# uP.net
KiCad netlist of a schematic drawn in Altium Designer
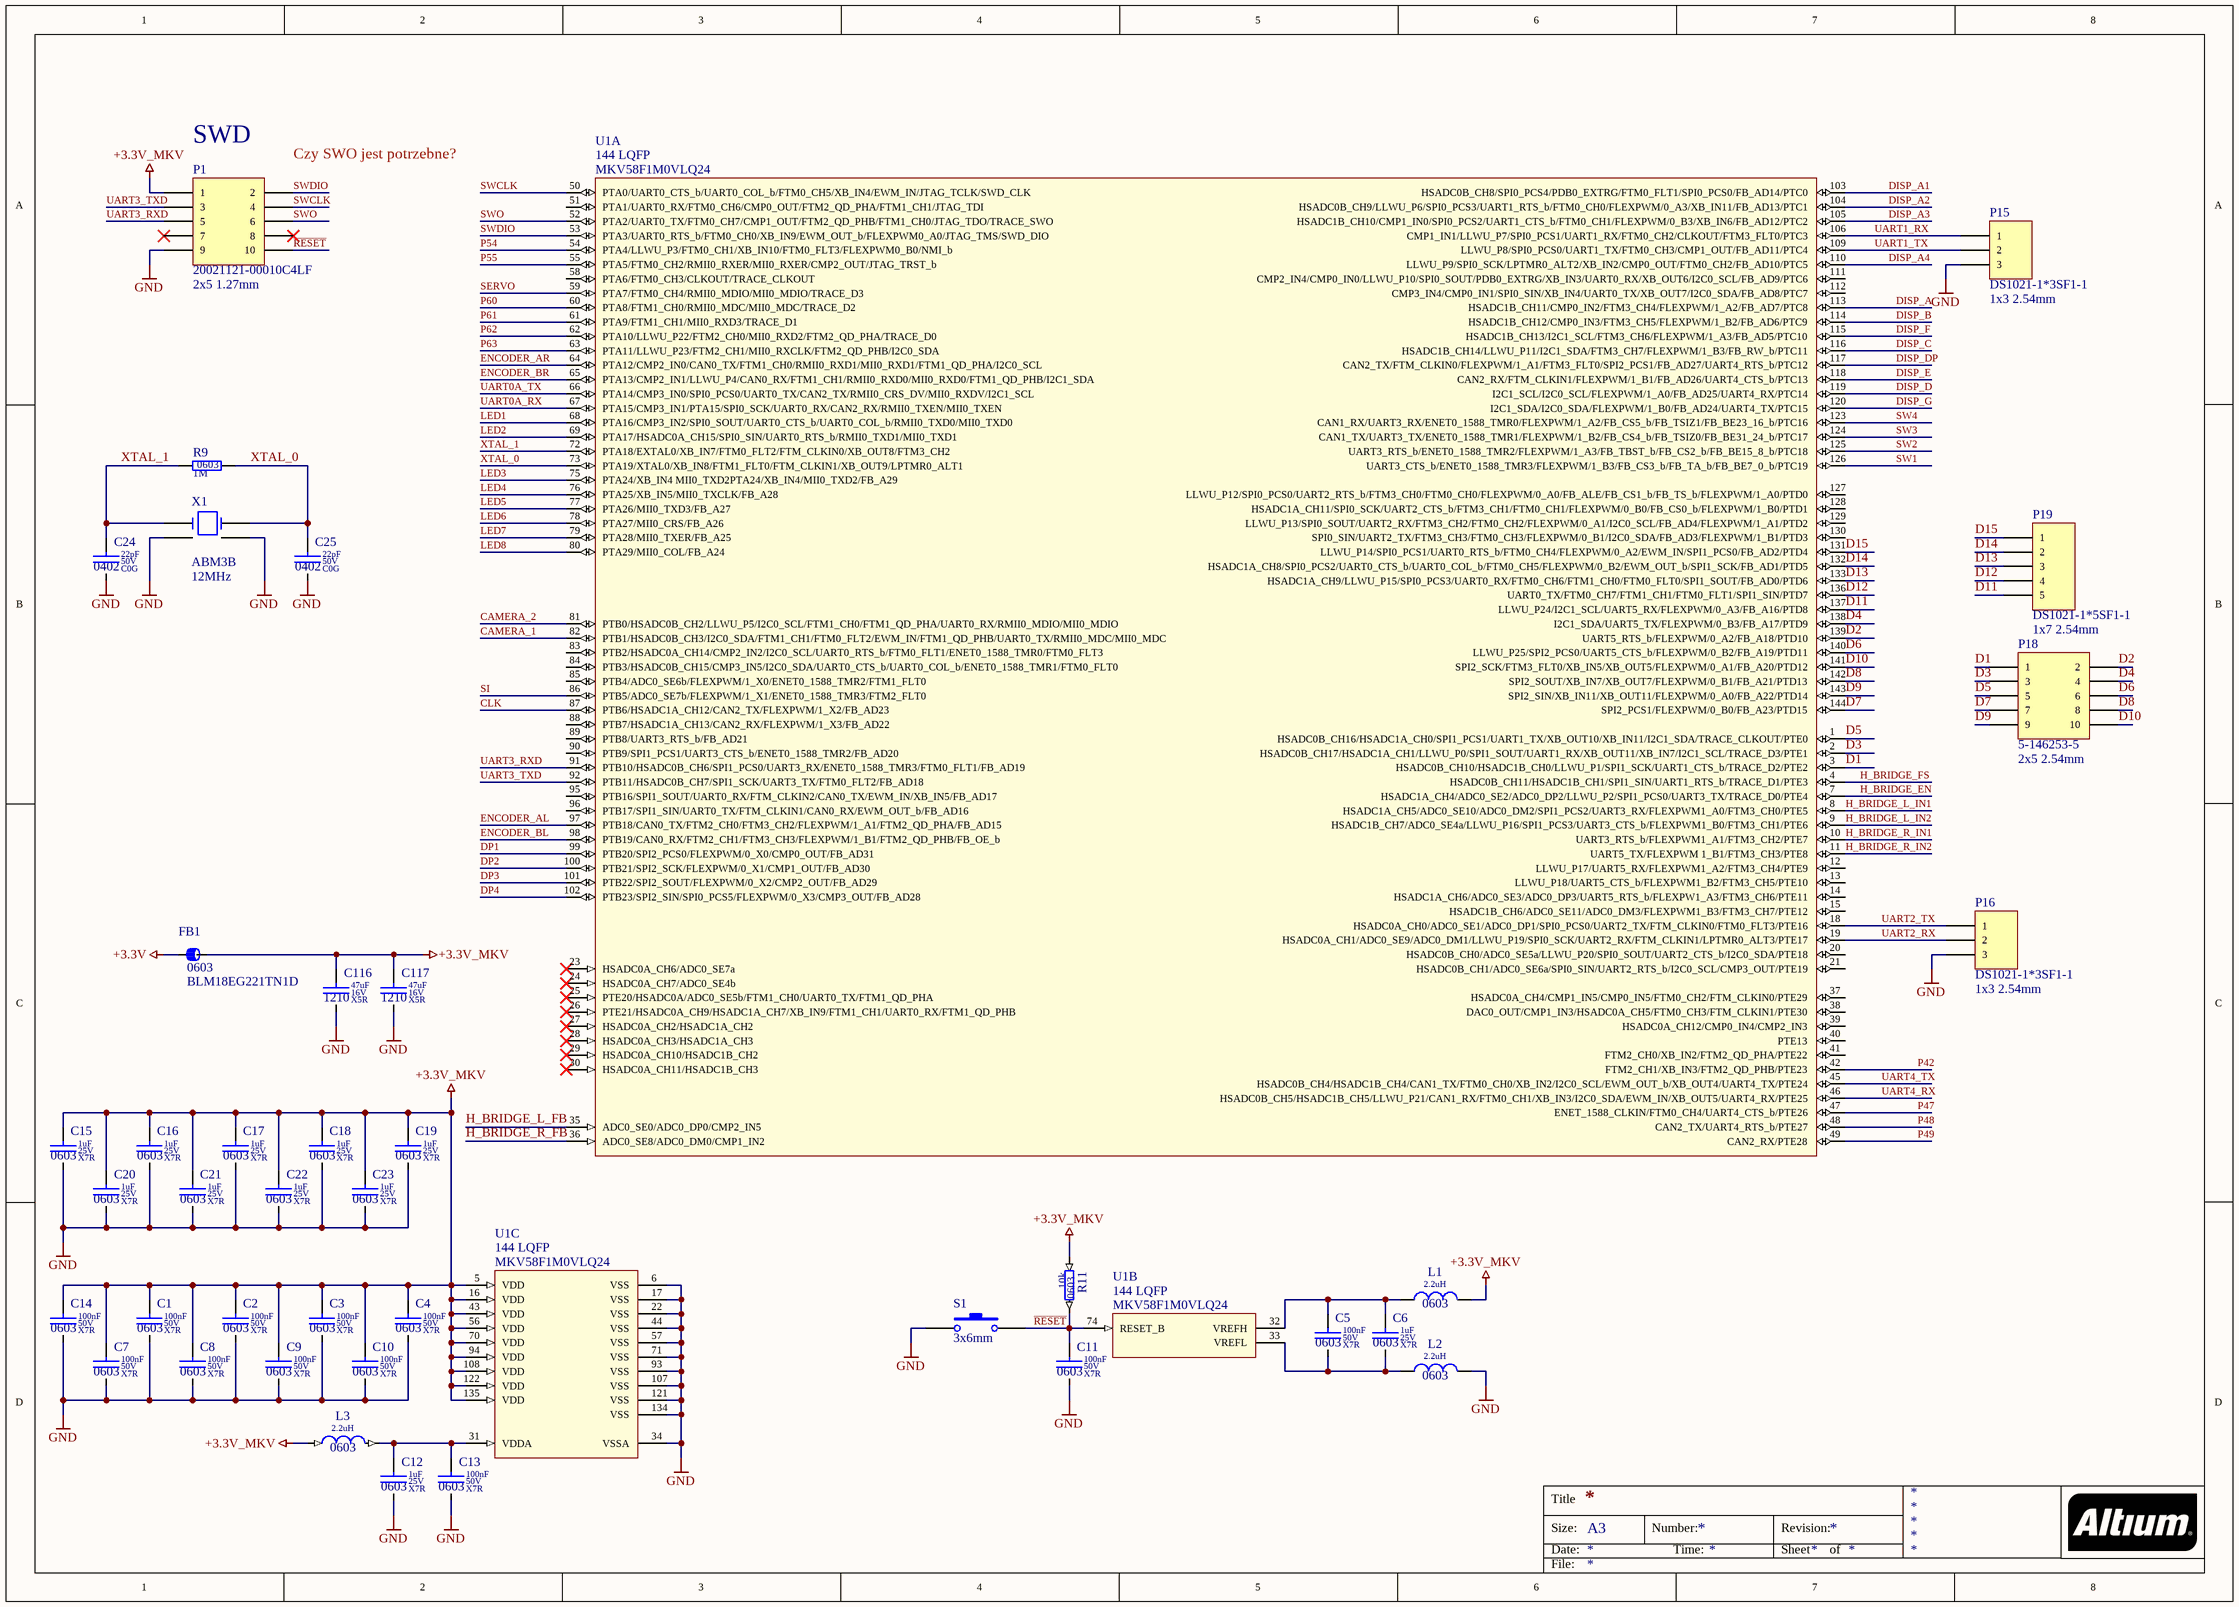
[diagram p0: uP.SchDoc]

(export (version "E")
  (design (tool "Eeschema 10.0.6"))
  (components
    (comp (ref "C1")
      (value "100nF")
      (footprint "C_0603_1608")
      (description "Capacitor")
      (fields
        (field (name "DIELECTRIC") "X7R")
        (field (name "VOLTAGE") "50V")
        (field (name "SCH_FOOTPRINT") "0603")
        (field (name "PART NUMBER") "C_100nF_50V_X7R_0603_5")
        (field (name "MANUFACTURER") "Samsung")
      )
      (libsource (lib "Library") (part "C"))
    )
    (comp (ref "C2")
      (value "100nF")
      (footprint "C_0603_1608")
      (description "Capacitor")
      (fields
        (field (name "DIELECTRIC") "X7R")
        (field (name "VOLTAGE") "50V")
        (field (name "SCH_FOOTPRINT") "0603")
        (field (name "PART NUMBER") "C_100nF_50V_X7R_0603_5")
        (field (name "MANUFACTURER") "Samsung")
      )
      (libsource (lib "Library") (part "C"))
    )
    (comp (ref "C3")
      (value "100nF")
      (footprint "C_0603_1608")
      (description "Capacitor")
      (fields
        (field (name "DIELECTRIC") "X7R")
        (field (name "VOLTAGE") "50V")
        (field (name "SCH_FOOTPRINT") "0603")
        (field (name "PART NUMBER") "C_100nF_50V_X7R_0603_5")
        (field (name "MANUFACTURER") "Samsung")
      )
      (libsource (lib "Library") (part "C"))
    )
    (comp (ref "C4")
      (value "100nF")
      (footprint "C_0603_1608")
      (description "Capacitor")
      (fields
        (field (name "DIELECTRIC") "X7R")
        (field (name "VOLTAGE") "50V")
        (field (name "SCH_FOOTPRINT") "0603")
        (field (name "PART NUMBER") "C_100nF_50V_X7R_0603_5")
        (field (name "MANUFACTURER") "Samsung")
      )
      (libsource (lib "Library") (part "C"))
    )
    (comp (ref "C5")
      (value "100nF")
      (footprint "C_0603_1608")
      (description "Capacitor")
      (fields
        (field (name "DIELECTRIC") "X7R")
        (field (name "VOLTAGE") "50V")
        (field (name "SCH_FOOTPRINT") "0603")
        (field (name "PART NUMBER") "C_100nF_50V_X7R_0603_5")
        (field (name "MANUFACTURER") "Samsung")
      )
      (libsource (lib "Library") (part "C"))
    )
    (comp (ref "C6")
      (value "1uF")
      (footprint "C_0603_1608")
      (description "Capacitor")
      (fields
        (field (name "DIELECTRIC") "X7R")
        (field (name "VOLTAGE") "25V")
        (field (name "SCH_FOOTPRINT") "0603")
        (field (name "PART NUMBER") "C_1uF_25V_X7R_0603_10")
        (field (name "MANUFACTURER") "Samsung")
      )
      (libsource (lib "Library") (part "C"))
    )
    (comp (ref "C7")
      (value "100nF")
      (footprint "C_0603_1608")
      (description "Capacitor")
      (fields
        (field (name "DIELECTRIC") "X7R")
        (field (name "VOLTAGE") "50V")
        (field (name "SCH_FOOTPRINT") "0603")
        (field (name "PART NUMBER") "C_100nF_50V_X7R_0603_5")
        (field (name "MANUFACTURER") "Samsung")
      )
      (libsource (lib "Library") (part "C"))
    )
    (comp (ref "C8")
      (value "100nF")
      (footprint "C_0603_1608")
      (description "Capacitor")
      (fields
        (field (name "DIELECTRIC") "X7R")
        (field (name "VOLTAGE") "50V")
        (field (name "SCH_FOOTPRINT") "0603")
        (field (name "PART NUMBER") "C_100nF_50V_X7R_0603_5")
        (field (name "MANUFACTURER") "Samsung")
      )
      (libsource (lib "Library") (part "C"))
    )
    (comp (ref "C9")
      (value "100nF")
      (footprint "C_0603_1608")
      (description "Capacitor")
      (fields
        (field (name "DIELECTRIC") "X7R")
        (field (name "VOLTAGE") "50V")
        (field (name "SCH_FOOTPRINT") "0603")
        (field (name "PART NUMBER") "C_100nF_50V_X7R_0603_5")
        (field (name "MANUFACTURER") "Samsung")
      )
      (libsource (lib "Library") (part "C"))
    )
    (comp (ref "C10")
      (value "100nF")
      (footprint "C_0603_1608")
      (description "Capacitor")
      (fields
        (field (name "DIELECTRIC") "X7R")
        (field (name "VOLTAGE") "50V")
        (field (name "SCH_FOOTPRINT") "0603")
        (field (name "PART NUMBER") "C_100nF_50V_X7R_0603_5")
        (field (name "MANUFACTURER") "Samsung")
      )
      (libsource (lib "Library") (part "C"))
    )
    (comp (ref "C11")
      (value "100nF")
      (footprint "C_0603_1608")
      (description "Capacitor")
      (fields
        (field (name "DIELECTRIC") "X7R")
        (field (name "VOLTAGE") "50V")
        (field (name "SCH_FOOTPRINT") "0603")
        (field (name "PART NUMBER") "C_100nF_50V_X7R_0603_5")
        (field (name "MANUFACTURER") "Samsung")
      )
      (libsource (lib "Library") (part "C"))
    )
    (comp (ref "C12")
      (value "1uF")
      (footprint "C_0603_1608")
      (description "Capacitor")
      (fields
        (field (name "DIELECTRIC") "X7R")
        (field (name "VOLTAGE") "25V")
        (field (name "SCH_FOOTPRINT") "0603")
        (field (name "PART NUMBER") "C_1uF_25V_X7R_0603_10")
        (field (name "MANUFACTURER") "Samsung")
      )
      (libsource (lib "Library") (part "C"))
    )
    (comp (ref "C13")
      (value "100nF")
      (footprint "C_0603_1608")
      (description "Capacitor")
      (fields
        (field (name "DIELECTRIC") "X7R")
        (field (name "VOLTAGE") "50V")
        (field (name "SCH_FOOTPRINT") "0603")
        (field (name "PART NUMBER") "C_100nF_50V_X7R_0603_5")
        (field (name "MANUFACTURER") "Samsung")
      )
      (libsource (lib "Library") (part "C"))
    )
    (comp (ref "C14")
      (value "100nF")
      (footprint "C_0603_1608")
      (description "Capacitor")
      (fields
        (field (name "DIELECTRIC") "X7R")
        (field (name "VOLTAGE") "50V")
        (field (name "SCH_FOOTPRINT") "0603")
        (field (name "PART NUMBER") "C_100nF_50V_X7R_0603_5")
        (field (name "MANUFACTURER") "Samsung")
      )
      (libsource (lib "Library") (part "C"))
    )
    (comp (ref "C15")
      (value "1uF")
      (footprint "C_0603_1608")
      (description "Capacitor")
      (fields
        (field (name "DIELECTRIC") "X7R")
        (field (name "VOLTAGE") "25V")
        (field (name "SCH_FOOTPRINT") "0603")
        (field (name "PART NUMBER") "C_1uF_25V_X7R_0603_10")
        (field (name "MANUFACTURER") "Samsung")
      )
      (libsource (lib "Library") (part "C"))
    )
    (comp (ref "C16")
      (value "1uF")
      (footprint "C_0603_1608")
      (description "Capacitor")
      (fields
        (field (name "DIELECTRIC") "X7R")
        (field (name "VOLTAGE") "25V")
        (field (name "SCH_FOOTPRINT") "0603")
        (field (name "PART NUMBER") "C_1uF_25V_X7R_0603_10")
        (field (name "MANUFACTURER") "Samsung")
      )
      (libsource (lib "Library") (part "C"))
    )
    (comp (ref "C17")
      (value "1uF")
      (footprint "C_0603_1608")
      (description "Capacitor")
      (fields
        (field (name "DIELECTRIC") "X7R")
        (field (name "VOLTAGE") "25V")
        (field (name "SCH_FOOTPRINT") "0603")
        (field (name "PART NUMBER") "C_1uF_25V_X7R_0603_10")
        (field (name "MANUFACTURER") "Samsung")
      )
      (libsource (lib "Library") (part "C"))
    )
    (comp (ref "C18")
      (value "1uF")
      (footprint "C_0603_1608")
      (description "Capacitor")
      (fields
        (field (name "DIELECTRIC") "X7R")
        (field (name "VOLTAGE") "25V")
        (field (name "SCH_FOOTPRINT") "0603")
        (field (name "PART NUMBER") "C_1uF_25V_X7R_0603_10")
        (field (name "MANUFACTURER") "Samsung")
      )
      (libsource (lib "Library") (part "C"))
    )
    (comp (ref "C19")
      (value "1uF")
      (footprint "C_0603_1608")
      (description "Capacitor")
      (fields
        (field (name "DIELECTRIC") "X7R")
        (field (name "VOLTAGE") "25V")
        (field (name "SCH_FOOTPRINT") "0603")
        (field (name "PART NUMBER") "C_1uF_25V_X7R_0603_10")
        (field (name "MANUFACTURER") "Samsung")
      )
      (libsource (lib "Library") (part "C"))
    )
    (comp (ref "C20")
      (value "1uF")
      (footprint "C_0603_1608")
      (description "Capacitor")
      (fields
        (field (name "DIELECTRIC") "X7R")
        (field (name "VOLTAGE") "25V")
        (field (name "SCH_FOOTPRINT") "0603")
        (field (name "PART NUMBER") "C_1uF_25V_X7R_0603_10")
        (field (name "MANUFACTURER") "Samsung")
      )
      (libsource (lib "Library") (part "C"))
    )
    (comp (ref "C21")
      (value "1uF")
      (footprint "C_0603_1608")
      (description "Capacitor")
      (fields
        (field (name "DIELECTRIC") "X7R")
        (field (name "VOLTAGE") "25V")
        (field (name "SCH_FOOTPRINT") "0603")
        (field (name "PART NUMBER") "C_1uF_25V_X7R_0603_10")
        (field (name "MANUFACTURER") "Samsung")
      )
      (libsource (lib "Library") (part "C"))
    )
    (comp (ref "C22")
      (value "1uF")
      (footprint "C_0603_1608")
      (description "Capacitor")
      (fields
        (field (name "DIELECTRIC") "X7R")
        (field (name "VOLTAGE") "25V")
        (field (name "SCH_FOOTPRINT") "0603")
        (field (name "PART NUMBER") "C_1uF_25V_X7R_0603_10")
        (field (name "MANUFACTURER") "Samsung")
      )
      (libsource (lib "Library") (part "C"))
    )
    (comp (ref "C23")
      (value "1uF")
      (footprint "C_0603_1608")
      (description "Capacitor")
      (fields
        (field (name "DIELECTRIC") "X7R")
        (field (name "VOLTAGE") "25V")
        (field (name "SCH_FOOTPRINT") "0603")
        (field (name "PART NUMBER") "C_1uF_25V_X7R_0603_10")
        (field (name "MANUFACTURER") "Samsung")
      )
      (libsource (lib "Library") (part "C"))
    )
    (comp (ref "C24")
      (value "22pF")
      (footprint "C_0402_1005")
      (description "Capacitor")
      (fields
        (field (name "DIELECTRIC") "C0G")
        (field (name "VOLTAGE") "50V")
        (field (name "SCH_FOOTPRINT") "0402")
        (field (name "PART NUMBER") "C_22pF_50V_C0G_0402_5")
        (field (name "MANUFACTURER") "AVX")
      )
      (libsource (lib "Library") (part "C"))
    )
    (comp (ref "C25")
      (value "22pF")
      (footprint "C_0402_1005")
      (description "Capacitor")
      (fields
        (field (name "DIELECTRIC") "C0G")
        (field (name "VOLTAGE") "50V")
        (field (name "SCH_FOOTPRINT") "0402")
        (field (name "PART NUMBER") "C_22pF_50V_C0G_0402_5")
        (field (name "MANUFACTURER") "AVX")
      )
      (libsource (lib "Library") (part "C"))
    )
    (comp (ref "C116")
      (value "47uF")
      (footprint "C_1210_3225")
      (description "Capacitor")
      (fields
        (field (name "DIELECTRIC") "X5R")
        (field (name "VOLTAGE") "16V")
        (field (name "SCH_FOOTPRINT") "1210")
        (field (name "PART NUMBER") "C_47uF_16V_X5R_1210_10")
        (field (name "MANUFACTURER") "Samsung")
      )
      (libsource (lib "Library") (part "C"))
    )
    (comp (ref "C117")
      (value "47uF")
      (footprint "C_1210_3225")
      (description "Capacitor")
      (fields
        (field (name "DIELECTRIC") "X5R")
        (field (name "VOLTAGE") "16V")
        (field (name "SCH_FOOTPRINT") "1210")
        (field (name "PART NUMBER") "C_47uF_16V_X5R_1210_10")
        (field (name "MANUFACTURER") "Samsung")
      )
      (libsource (lib "Library") (part "C"))
    )
    (comp (ref "FB1")
      (value "BLM18EG221TN1D")
      (footprint "FB_0603_1608")
      (description "Ferrite Bead")
      (fields
        (field (name "PART NUMBER") "FB_BLM18EG221TN1D")
        (field (name "SCH_FOOTPRINT") "0603")
        (field (name "MANUFACTURER") "Murata")
      )
      (libsource (lib "Library") (part "FB"))
    )
    (comp (ref "L1")
      (value "2.2uH")
      (footprint "L_0603_1608")
      (description "Induction")
      (fields
        (field (name "SCH_FOOTPRINT") "0603")
        (field (name "PART NUMBER") "L_2.2uH_130mA_0603")
        (field (name "MANUFACTURER") "TDK")
      )
      (libsource (lib "") (part "L_1"))
    )
    (comp (ref "L2")
      (value "2.2uH")
      (footprint "L_0603_1608")
      (description "Induction")
      (fields
        (field (name "SCH_FOOTPRINT") "0603")
        (field (name "PART NUMBER") "L_2.2uH_130mA_0603")
        (field (name "MANUFACTURER") "TDK")
      )
      (libsource (lib "") (part "L_1"))
    )
    (comp (ref "L3")
      (value "2.2uH")
      (footprint "L_0603_1608")
      (description "Induction")
      (fields
        (field (name "SCH_FOOTPRINT") "0603")
        (field (name "PART NUMBER") "L_2.2uH_130mA_0603")
        (field (name "MANUFACTURER") "TDK")
      )
      (libsource (lib "Library") (part "L"))
    )
    (comp (ref "P1")
      (value "20021121-00010C4LF")
      (footprint "P_HEADER_2x5_1.27")
      (description "Header, 10-Pin, Dual row")
      (fields
        (field (name "PART NUMBER") "P_HEADER_2x5_1.27")
        (field (name "SCH_FOOTPRINT") "2x5 1.27mm")
        (field (name "MANUFACTURER") "FCI")
      )
      (libsource (lib "Library") (part "P_HEADER_2x5"))
    )
    (comp (ref "P15")
      (value "DS1021-1*3SF1-1")
      (footprint "P_HEADER_1x3_2.54")
      (description "Header, 3-Pin")
      (fields
        (field (name "PART NUMBER") "P_HEADER_1x3_2.54")
        (field (name "SCH_FOOTPRINT") "1x3 2.54mm")
        (field (name "MANUFACTURER") "Connfly")
      )
      (libsource (lib "Library") (part "P_HEADER_1x3"))
    )
    (comp (ref "P16")
      (value "DS1021-1*3SF1-1")
      (footprint "P_HEADER_1x3_2.54")
      (description "Header, 3-Pin")
      (fields
        (field (name "PART NUMBER") "P_HEADER_1x3_2.54")
        (field (name "SCH_FOOTPRINT") "1x3 2.54mm")
        (field (name "MANUFACTURER") "Connfly")
      )
      (libsource (lib "Library") (part "P_HEADER_1x3"))
    )
    (comp (ref "P18")
      (value "5-146253-5")
      (footprint "P_HEADER_2x5_2.54")
      (description "Header, 10-Pin, Dual row")
      (fields
        (field (name "PART NUMBER") "P_HEADER_2x5_2.54")
        (field (name "SCH_FOOTPRINT") "2x5 2.54mm")
        (field (name "MANUFACTURER") "TE Connectivity")
      )
      (libsource (lib "Library") (part "P_HEADER_2x5"))
    )
    (comp (ref "P19")
      (value "DS1021-1*5SF1-1")
      (footprint "P_HEADER_1x5_2.54")
      (description "Header, 5-Pin")
      (fields
        (field (name "PART NUMBER") "P_HEADER_1x5_2.54")
        (field (name "SCH_FOOTPRINT") "1x7 2.54mm")
        (field (name "MANUFACTURER") "Connfly")
      )
      (libsource (lib "Library") (part "P_HEADER_1x5"))
    )
    (comp (ref "R9")
      (value "1M")
      (footprint "R_0603_1608")
      (fields
        (field (name "SCH_FOOTPRINT") "0603")
        (field (name "PART NUMBER") "R_1M_0603_1")
        (field (name "VOLTAGE") "50V")
        (field (name "POWER") "100mW")
      )
      (libsource (lib "") (part "R_1"))
    )
    (comp (ref "R11")
      (value "10k")
      (footprint "R_0603_1608")
      (fields
        (field (name "SCH_FOOTPRINT") "0603")
        (field (name "PART NUMBER") "R_10k_0603_1")
        (field (name "VOLTAGE") "75V")
        (field (name "POWER") "100mW")
      )
      (libsource (lib "Library") (part "R"))
    )
    (comp (ref "S1")
      (value "3x6mm")
      (footprint "S_TACTSWITCH3x6")
      (description "Tact Switch")
      (fields
        (field (name "PART NUMBER") "S_TACTSWITCH")
        (field (name "SCH_FOOTPRINT") "3x6mm")
        (field (name "MANUFACTURER") "Ninigi")
      )
      (libsource (lib "Library") (part "S_TACTSWITCH"))
    )
    (comp (ref "U1")
      (value "MKV58F1M0VLQ24")
      (footprint "LQFP144_20x20")
      (description "240 MHz Cortex-M7 based MCU for Real-time")
      (fields
        (field (name "SCH_FOOTPRINT") "144 LQFP")
        (field (name "PART NUMBER") "U_MKV58F1M0VLQ24")
        (field (name "MANUFACTURER") "NXP")
      )
      (libsource (lib "Library") (part "U_MKV58F1M0VLQ24"))
    )
    (comp (ref "X1")
      (value "12MHz")
      (footprint "X_ABM3B_5X3X11")
      (fields
        (field (name "PART NUMBER") "X_12M8HZ_ABM3B")
        (field (name "SCH_FOOTPRINT") "ABM3B")
        (field (name "Comment") "X_ABM3B")
      )
      (libsource (lib "Library") (part "X_ABM3B"))
    )
  )
  (nets
    (net (code "1") (name "+3.3V") (class "Default") (node (ref "FB1") (pin "1") (pintype "input")))
    (net (code "2") (name "+3.3V_MKV") (class "Default")
      (node (ref "C1") (pin "1") (pinfunction "1_1") (pintype "passive"))
      (node (ref "C10") (pin "1") (pinfunction "1_1") (pintype "passive"))
      (node (ref "C116") (pin "1") (pinfunction "1_1") (pintype "passive"))
      (node (ref "C117") (pin "1") (pinfunction "1_1") (pintype "passive"))
      (node (ref "C14") (pin "1") (pinfunction "1_1") (pintype "passive"))
      (node (ref "C15") (pin "1") (pinfunction "1_1") (pintype "passive"))
      (node (ref "C16") (pin "1") (pinfunction "1_1") (pintype "passive"))
      (node (ref "C17") (pin "1") (pinfunction "1_1") (pintype "passive"))
      (node (ref "C18") (pin "1") (pinfunction "1_1") (pintype "passive"))
      (node (ref "C19") (pin "1") (pinfunction "1_1") (pintype "passive"))
      (node (ref "C2") (pin "1") (pinfunction "1_1") (pintype "passive"))
      (node (ref "C20") (pin "1") (pinfunction "1_1") (pintype "passive"))
      (node (ref "C21") (pin "1") (pinfunction "1_1") (pintype "passive"))
      (node (ref "C22") (pin "1") (pinfunction "1_1") (pintype "passive"))
      (node (ref "C23") (pin "1") (pinfunction "1_1") (pintype "passive"))
      (node (ref "C3") (pin "1") (pinfunction "1_1") (pintype "passive"))
      (node (ref "C4") (pin "1") (pinfunction "1_1") (pintype "passive"))
      (node (ref "C7") (pin "1") (pinfunction "1_1") (pintype "passive"))
      (node (ref "C8") (pin "1") (pinfunction "1_1") (pintype "passive"))
      (node (ref "C9") (pin "1") (pinfunction "1_1") (pintype "passive"))
      (node (ref "FB1") (pin "2") (pintype "output"))
      (node (ref "L1") (pin "2") (pinfunction "2_2") (pintype "passive"))
      (node (ref "L3") (pin "1") (pinfunction "1_1") (pintype "input"))
      (node (ref "P1") (pin "1") (pinfunction "1_1") (pintype "passive"))
      (node (ref "R11") (pin "1") (pinfunction "1_1") (pintype "input"))
      (node (ref "U1") (pin "108") (pinfunction "VDD_108") (pintype "input"))
      (node (ref "U1") (pin "122") (pinfunction "VDD_122") (pintype "input"))
      (node (ref "U1") (pin "135") (pinfunction "VDD_135") (pintype "input"))
      (node (ref "U1") (pin "16") (pinfunction "VDD_16") (pintype "input"))
      (node (ref "U1") (pin "43") (pinfunction "VDD_43") (pintype "input"))
      (node (ref "U1") (pin "5") (pinfunction "VDD_5") (pintype "input"))
      (node (ref "U1") (pin "56") (pinfunction "VDD_56") (pintype "input"))
      (node (ref "U1") (pin "70") (pinfunction "VDD_70") (pintype "input"))
      (node (ref "U1") (pin "94") (pinfunction "VDD_94") (pintype "input"))
    )
    (net (code "3") (name "/CAMERA_1") (class "Default")
      (node (ref "U1") (pin "82") (pinfunction "PTB1/HSADC0B_CH3/I2C0_SDA/FTM1_CH1/FTM0_FLT2/EWM_IN/FTM1_QD_PHB/UART0_TX/RMII0_MDC/MII0_MDC_82") (pintype "bidirectional"))
    )
    (net (code "4") (name "/CAMERA_2") (class "Default")
      (node (ref "U1") (pin "81") (pinfunction "PTB0/HSADC0B_CH2/LLWU_P5/I2C0_SCL/FTM1_CH0/FTM1_QD_PHA/UART0_RX/RMII0_MDIO/MII0_MDIO_81") (pintype "bidirectional"))
    )
    (net (code "5") (name "/CLK") (class "Default")
      (node (ref "U1") (pin "87") (pinfunction "PTB6/HSADC1A_CH12/CAN2_TX/FLEXPWM/1_X2/FB_AD23_87") (pintype "bidirectional"))
    )
    (net (code "6") (name "/D1") (class "Default")
      (node (ref "P18") (pin "1") (pinfunction "1_1") (pintype "passive"))
      (node (ref "U1") (pin "3") (pinfunction "HSADC0B_CH10/HSADC1B_CH0/LLWU_P1/SPI1_SCK/UART1_CTS_b/TRACE_D2/PTE2_3") (pintype "bidirectional"))
    )
    (net (code "7") (name "/D2") (class "Default")
      (node (ref "P18") (pin "2") (pinfunction "2_2") (pintype "passive"))
      (node (ref "U1") (pin "139") (pinfunction "UART5_RTS_b/FLEXPWM/0_A2/FB_A18/PTD10_139") (pintype "bidirectional"))
    )
    (net (code "8") (name "/D3") (class "Default")
      (node (ref "P18") (pin "3") (pinfunction "3_3") (pintype "passive"))
      (node (ref "U1") (pin "2") (pinfunction "HSADC0B_CH17/HSADC1A_CH1/LLWU_P0/SPI1_SOUT/UART1_RX/XB_OUT11/XB_IN7/I2C1_SCL/TRACE_D3/PTE1_2") (pintype "bidirectional"))
    )
    (net (code "9") (name "/D4") (class "Default")
      (node (ref "P18") (pin "4") (pinfunction "4_4") (pintype "passive"))
      (node (ref "U1") (pin "138") (pinfunction "I2C1_SDA/UART5_TX/FLEXPWM/0_B3/FB_A17/PTD9_138") (pintype "bidirectional"))
    )
    (net (code "10") (name "/D5") (class "Default")
      (node (ref "P18") (pin "5") (pinfunction "5_5") (pintype "passive"))
      (node (ref "U1") (pin "1") (pinfunction "HSADC0B_CH16/HSADC1A_CH0/SPI1_PCS1/UART1_TX/XB_OUT10/XB_IN11/I2C1_SDA/TRACE_CLKOUT/PTE0_1") (pintype "bidirectional"))
    )
    (net (code "11") (name "/D6") (class "Default")
      (node (ref "P18") (pin "6") (pinfunction "6_6") (pintype "passive"))
      (node (ref "U1") (pin "140") (pinfunction "LLWU_P25/SPI2_PCS0/UART5_CTS_b/FLEXPWM/0_B2/FB_A19/PTD11_140") (pintype "bidirectional"))
    )
    (net (code "12") (name "/D7") (class "Default")
      (node (ref "P18") (pin "7") (pinfunction "7_7") (pintype "passive"))
      (node (ref "U1") (pin "144") (pinfunction "SPI2_PCS1/FLEXPWM/0_B0/FB_A23/PTD15_144") (pintype "bidirectional"))
    )
    (net (code "13") (name "/D8") (class "Default")
      (node (ref "P18") (pin "8") (pinfunction "8_8") (pintype "passive"))
      (node (ref "U1") (pin "142") (pinfunction "SPI2_SOUT/XB_IN7/XB_OUT7/FLEXPWM/0_B1/FB_A21/PTD13_142") (pintype "bidirectional"))
    )
    (net (code "14") (name "/D9") (class "Default")
      (node (ref "P18") (pin "9") (pinfunction "9_9") (pintype "passive"))
      (node (ref "U1") (pin "143") (pinfunction "SPI2_SIN/XB_IN11/XB_OUT11/FLEXPWM/0_A0/FB_A22/PTD14_143") (pintype "bidirectional"))
    )
    (net (code "15") (name "/D10") (class "Default")
      (node (ref "P18") (pin "10") (pinfunction "10_10") (pintype "passive"))
      (node (ref "U1") (pin "141") (pinfunction "SPI2_SCK/FTM3_FLT0/XB_IN5/XB_OUT5/FLEXPWM/0_A1/FB_A20/PTD12_141") (pintype "bidirectional"))
    )
    (net (code "16") (name "/D11") (class "Default")
      (node (ref "P19") (pin "5") (pinfunction "5_5") (pintype "passive"))
      (node (ref "U1") (pin "137") (pinfunction "LLWU_P24/I2C1_SCL/UART5_RX/FLEXPWM/0_A3/FB_A16/PTD8_137") (pintype "bidirectional"))
    )
    (net (code "17") (name "/D12") (class "Default")
      (node (ref "P19") (pin "4") (pinfunction "4_4") (pintype "passive"))
      (node (ref "U1") (pin "136") (pinfunction "UART0_TX/FTM0_CH7/FTM1_CH1/FTM0_FLT1/SPI1_SIN/PTD7_136") (pintype "bidirectional"))
    )
    (net (code "18") (name "/D13") (class "Default")
      (node (ref "P19") (pin "3") (pinfunction "3_3") (pintype "passive"))
      (node (ref "U1") (pin "133") (pinfunction "HSADC1A_CH9/LLWU_P15/SPI0_PCS3/UART0_RX/FTM0_CH6/FTM1_CH0/FTM0_FLT0/SPI1_SOUT/FB_AD0/PTD6_133") (pintype "bidirectional"))
    )
    (net (code "19") (name "/D14") (class "Default")
      (node (ref "P19") (pin "2") (pinfunction "2_2") (pintype "passive"))
      (node (ref "U1") (pin "132") (pinfunction "HSADC1A_CH8/SPI0_PCS2/UART0_CTS_b/UART0_COL_b/FTM0_CH5/FLEXPWM/0_B2/EWM_OUT_b/SPI1_SCK/FB_AD1/PTD5_132") (pintype "bidirectional"))
    )
    (net (code "20") (name "/D15") (class "Default")
      (node (ref "P19") (pin "1") (pinfunction "1_1") (pintype "passive"))
      (node (ref "U1") (pin "131") (pinfunction "LLWU_P14/SPI0_PCS1/UART0_RTS_b/FTM0_CH4/FLEXPWM/0_A2/EWM_IN/SPI1_PCS0/FB_AD2/PTD4_131") (pintype "bidirectional"))
    )
    (net (code "21") (name "/DISP_A") (class "Default")
      (node (ref "U1") (pin "113") (pinfunction "HSADC1B_CH11/CMP0_IN2/FTM3_CH4/FLEXPWM/1_A2/FB_AD7/PTC8_113") (pintype "bidirectional"))
    )
    (net (code "22") (name "/DISP_A1") (class "Default")
      (node (ref "U1") (pin "103") (pinfunction "HSADC0B_CH8/SPI0_PCS4/PDB0_EXTRG/FTM0_FLT1/SPI0_PCS0/FB_AD14/PTC0_103") (pintype "bidirectional"))
    )
    (net (code "23") (name "/DISP_A2") (class "Default")
      (node (ref "U1") (pin "104") (pinfunction "HSADC0B_CH9/LLWU_P6/SPI0_PCS3/UART1_RTS_b/FTM0_CH0/FLEXPWM/0_A3/XB_IN11/FB_AD13/PTC1_104") (pintype "bidirectional"))
    )
    (net (code "24") (name "/DISP_A3") (class "Default")
      (node (ref "U1") (pin "105") (pinfunction "HSADC1B_CH10/CMP1_IN0/SPI0_PCS2/UART1_CTS_b/FTM0_CH1/FLEXPWM/0_B3/XB_IN6/FB_AD12/PTC2_105") (pintype "bidirectional"))
    )
    (net (code "25") (name "/DISP_A4") (class "Default")
      (node (ref "U1") (pin "110") (pinfunction "LLWU_P9/SPI0_SCK/LPTMR0_ALT2/XB_IN2/CMP0_OUT/FTM0_CH2/FB_AD10/PTC5_110") (pintype "bidirectional"))
    )
    (net (code "26") (name "/DISP_B") (class "Default")
      (node (ref "U1") (pin "114") (pinfunction "HSADC1B_CH12/CMP0_IN3/FTM3_CH5/FLEXPWM/1_B2/FB_AD6/PTC9_114") (pintype "bidirectional"))
    )
    (net (code "27") (name "/DISP_C") (class "Default")
      (node (ref "U1") (pin "116") (pinfunction "HSADC1B_CH14/LLWU_P11/I2C1_SDA/FTM3_CH7/FLEXPWM/1_B3/FB_RW_b/PTC11_116") (pintype "bidirectional"))
    )
    (net (code "28") (name "/DISP_D") (class "Default")
      (node (ref "U1") (pin "119") (pinfunction "I2C1_SCL/I2C0_SCL/FLEXPWM/1_A0/FB_AD25/UART4_RX/PTC14_119") (pintype "bidirectional"))
    )
    (net (code "29") (name "/DISP_DP") (class "Default")
      (node (ref "U1") (pin "117") (pinfunction "CAN2_TX/FTM_CLKIN0/FLEXPWM/1_A1/FTM3_FLT0/SPI2_PCS1/FB_AD27/UART4_RTS_b/PTC12_117") (pintype "bidirectional"))
    )
    (net (code "30") (name "/DISP_E") (class "Default")
      (node (ref "U1") (pin "118") (pinfunction "CAN2_RX/FTM_CLKIN1/FLEXPWM/1_B1/FB_AD26/UART4_CTS_b/PTC13_118") (pintype "bidirectional"))
    )
    (net (code "31") (name "/DISP_F") (class "Default")
      (node (ref "U1") (pin "115") (pinfunction "HSADC1B_CH13/I2C1_SCL/FTM3_CH6/FLEXPWM/1_A3/FB_AD5/PTC10_115") (pintype "bidirectional"))
    )
    (net (code "32") (name "/DISP_G") (class "Default")
      (node (ref "U1") (pin "120") (pinfunction "I2C1_SDA/I2C0_SDA/FLEXPWM/1_B0/FB_AD24/UART4_TX/PTC15_120") (pintype "bidirectional"))
    )
    (net (code "33") (name "/DP1") (class "Default")
      (node (ref "U1") (pin "99") (pinfunction "PTB20/SPI2_PCS0/FLEXPWM/0_X0/CMP0_OUT/FB_AD31_99") (pintype "bidirectional"))
    )
    (net (code "34") (name "/DP2") (class "Default")
      (node (ref "U1") (pin "100") (pinfunction "PTB21/SPI2_SCK/FLEXPWM/0_X1/CMP1_OUT/FB_AD30_100") (pintype "bidirectional"))
    )
    (net (code "35") (name "/DP3") (class "Default")
      (node (ref "U1") (pin "101") (pinfunction "PTB22/SPI2_SOUT/FLEXPWM/0_X2/CMP2_OUT/FB_AD29_101") (pintype "bidirectional"))
    )
    (net (code "36") (name "/DP4") (class "Default")
      (node (ref "U1") (pin "102") (pinfunction "PTB23/SPI2_SIN/SPI0_PCS5/FLEXPWM/0_X3/CMP3_OUT/FB_AD28_102") (pintype "bidirectional"))
    )
    (net (code "37") (name "/ENCODER_AL") (class "Default")
      (node (ref "U1") (pin "97") (pinfunction "PTB18/CAN0_TX/FTM2_CH0/FTM3_CH2/FLEXPWM/1_A1/FTM2_QD_PHA/FB_AD15_97") (pintype "bidirectional"))
    )
    (net (code "38") (name "/ENCODER_AR") (class "Default")
      (node (ref "U1") (pin "64") (pinfunction "PTA12/CMP2_IN0/CAN0_TX/FTM1_CH0/RMII0_RXD1/MII0_RXD1/FTM1_QD_PHA/I2C0_SCL_64") (pintype "bidirectional"))
    )
    (net (code "39") (name "/ENCODER_BL") (class "Default")
      (node (ref "U1") (pin "98") (pinfunction "PTB19/CAN0_RX/FTM2_CH1/FTM3_CH3/FLEXPWM/1_B1/FTM2_QD_PHB/FB_OE_b_98") (pintype "bidirectional"))
    )
    (net (code "40") (name "/ENCODER_BR") (class "Default")
      (node (ref "U1") (pin "65") (pinfunction "PTA13/CMP2_IN1/LLWU_P4/CAN0_RX/FTM1_CH1/RMII0_RXD0/MII0_RXD0/FTM1_QD_PHB/I2C1_SDA_65") (pintype "bidirectional"))
    )
    (net (code "41") (name "/H_BRIDGE_EN") (class "Default")
      (node (ref "U1") (pin "7") (pinfunction "HSADC1A_CH4/ADC0_SE2/ADC0_DP2/LLWU_P2/SPI1_PCS0/UART3_TX/TRACE_D0/PTE4_7") (pintype "bidirectional"))
    )
    (net (code "42") (name "/H_BRIDGE_FS") (class "Default")
      (node (ref "U1") (pin "4") (pinfunction "HSADC0B_CH11/HSADC1B_CH1/SPI1_SIN/UART1_RTS_b/TRACE_D1/PTE3_4") (pintype "bidirectional"))
    )
    (net (code "43") (name "/H_BRIDGE_L_FB") (class "Default")
      (node (ref "U1") (pin "35") (pinfunction "ADC0_SE0/ADC0_DP0/CMP2_IN5_35") (pintype "input"))
    )
    (net (code "44") (name "/H_BRIDGE_L_IN1") (class "Default")
      (node (ref "U1") (pin "8") (pinfunction "HSADC1A_CH5/ADC0_SE10/ADC0_DM2/SPI1_PCS2/UART3_RX/FLEXPWM1_A0/FTM3_CH0/PTE5_8") (pintype "bidirectional"))
    )
    (net (code "45") (name "/H_BRIDGE_L_IN2") (class "Default")
      (node (ref "U1") (pin "9") (pinfunction "HSADC1B_CH7/ADC0_SE4a/LLWU_P16/SPI1_PCS3/UART3_CTS_b/FLEXPWM1_B0/FTM3_CH1/PTE6_9") (pintype "bidirectional"))
    )
    (net (code "46") (name "/H_BRIDGE_R_FB") (class "Default")
      (node (ref "U1") (pin "36") (pinfunction "ADC0_SE8/ADC0_DM0/CMP1_IN2_36") (pintype "input"))
    )
    (net (code "47") (name "/H_BRIDGE_R_IN1") (class "Default")
      (node (ref "U1") (pin "10") (pinfunction "UART3_RTS_b/FLEXPWM1_A1/FTM3_CH2/PTE7_10") (pintype "bidirectional"))
    )
    (net (code "48") (name "/H_BRIDGE_R_IN2") (class "Default")
      (node (ref "U1") (pin "11") (pinfunction "UART5_TX/FLEXPWM_1_B1/FTM3_CH3/PTE8_11") (pintype "bidirectional"))
    )
    (net (code "49") (name "/LED1") (class "Default")
      (node (ref "U1") (pin "68") (pinfunction "PTA16/CMP3_IN2/SPI0_SOUT/UART0_CTS_b/UART0_COL_b/RMII0_TXD0/MII0_TXD0_68") (pintype "bidirectional"))
    )
    (net (code "50") (name "/LED2") (class "Default")
      (node (ref "U1") (pin "69") (pinfunction "PTA17/HSADC0A_CH15/SPI0_SIN/UART0_RTS_b/RMII0_TXD1/MII0_TXD1_69") (pintype "bidirectional"))
    )
    (net (code "51") (name "/LED3") (class "Default")
      (node (ref "U1") (pin "75") (pinfunction "PTA24/XB_IN4_MII0_TXD2PTA24/XB_IN4/MII0_TXD2/FB_A29_75") (pintype "bidirectional"))
    )
    (net (code "52") (name "/LED4") (class "Default")
      (node (ref "U1") (pin "76") (pinfunction "PTA25/XB_IN5/MII0_TXCLK/FB_A28_76") (pintype "bidirectional"))
    )
    (net (code "53") (name "/LED5") (class "Default")
      (node (ref "U1") (pin "77") (pinfunction "PTA26/MII0_TXD3/FB_A27_77") (pintype "bidirectional"))
    )
    (net (code "54") (name "/LED6") (class "Default")
      (node (ref "U1") (pin "78") (pinfunction "PTA27/MII0_CRS/FB_A26_78") (pintype "bidirectional"))
    )
    (net (code "55") (name "/LED7") (class "Default")
      (node (ref "U1") (pin "79") (pinfunction "PTA28/MII0_TXER/FB_A25_79") (pintype "bidirectional"))
    )
    (net (code "56") (name "/LED8") (class "Default")
      (node (ref "U1") (pin "80") (pinfunction "PTA29/MII0_COL/FB_A24_80") (pintype "bidirectional"))
    )
    (net (code "57") (name "/P42") (class "Default")
      (node (ref "U1") (pin "42") (pinfunction "FTM2_CH1/XB_IN3/FTM2_QD_PHB/PTE23_42") (pintype "bidirectional"))
    )
    (net (code "58") (name "/P47") (class "Default")
      (node (ref "U1") (pin "47") (pinfunction "ENET_1588_CLKIN/FTM0_CH4/UART4_CTS_b/PTE26_47") (pintype "bidirectional"))
    )
    (net (code "59") (name "/P48") (class "Default")
      (node (ref "U1") (pin "48") (pinfunction "CAN2_TX/UART4_RTS_b/PTE27_48") (pintype "bidirectional"))
    )
    (net (code "60") (name "/P49") (class "Default")
      (node (ref "U1") (pin "49") (pinfunction "CAN2_RX/PTE28_49") (pintype "bidirectional"))
    )
    (net (code "61") (name "/P54") (class "Default")
      (node (ref "U1") (pin "54") (pinfunction "PTA4/LLWU_P3/FTM0_CH1/XB_IN10/FTM0_FLT3/FLEXPWM0_B0/NMI_b_54") (pintype "bidirectional"))
    )
    (net (code "62") (name "/P55") (class "Default")
      (node (ref "U1") (pin "55") (pinfunction "PTA5/FTM0_CH2/RMII0_RXER/MII0_RXER/CMP2_OUT/JTAG_TRST_b_55") (pintype "bidirectional"))
    )
    (net (code "63") (name "/P60") (class "Default")
      (node (ref "U1") (pin "60") (pinfunction "PTA8/FTM1_CH0/RMII0_MDC/MII0_MDC/TRACE_D2_60") (pintype "bidirectional"))
    )
    (net (code "64") (name "/P61") (class "Default")
      (node (ref "U1") (pin "61") (pinfunction "PTA9/FTM1_CH1/MII0_RXD3/TRACE_D1_61") (pintype "bidirectional"))
    )
    (net (code "65") (name "/P62") (class "Default")
      (node (ref "U1") (pin "62") (pinfunction "PTA10/LLWU_P22/FTM2_CH0/MII0_RXD2/FTM2_QD_PHA/TRACE_D0_62") (pintype "bidirectional"))
    )
    (net (code "66") (name "/P63") (class "Default")
      (node (ref "U1") (pin "63") (pinfunction "PTA11/LLWU_P23/FTM2_CH1/MII0_RXCLK/FTM2_QD_PHB/I2C0_SDA_63") (pintype "bidirectional"))
    )
    (net (code "67") (name "/SERVO") (class "Default")
      (node (ref "U1") (pin "59") (pinfunction "PTA7/FTM0_CH4/RMII0_MDIO/MII0_MDIO/TRACE_D3_59") (pintype "bidirectional"))
    )
    (net (code "68") (name "/SI") (class "Default")
      (node (ref "U1") (pin "86") (pinfunction "PTB5/ADC0_SE7b/FLEXPWM/1_X1/ENET0_1588_TMR3/FTM2_FLT0_86") (pintype "bidirectional"))
    )
    (net (code "69") (name "/SW1") (class "Default")
      (node (ref "U1") (pin "126") (pinfunction "UART3_CTS_b/ENET0_1588_TMR3/FLEXPWM/1_B3/FB_CS3_b/FB_TA_b/FB_BE7_0_b/PTC19_126") (pintype "bidirectional"))
    )
    (net (code "70") (name "/SW2") (class "Default")
      (node (ref "U1") (pin "125") (pinfunction "UART3_RTS_b/ENET0_1588_TMR2/FLEXPWM/1_A3/FB_TBST_b/FB_CS2_b/FB_BE15_8_b/PTC18_125") (pintype "bidirectional"))
    )
    (net (code "71") (name "/SW3") (class "Default")
      (node (ref "U1") (pin "124") (pinfunction "CAN1_TX/UART3_TX/ENET0_1588_TMR1/FLEXPWM/1_B2/FB_CS4_b/FB_TSIZ0/FB_BE31_24_b/PTC17_124") (pintype "bidirectional"))
    )
    (net (code "72") (name "/SW4") (class "Default")
      (node (ref "U1") (pin "123") (pinfunction "CAN1_RX/UART3_RX/ENET0_1588_TMR0/FLEXPWM/1_A2/FB_CS5_b/FB_TSIZ1/FB_BE23_16_b/PTC16_123") (pintype "bidirectional"))
    )
    (net (code "73") (name "/SWCLK") (class "Default")
      (node (ref "P1") (pin "4") (pinfunction "4_4") (pintype "passive"))
      (node (ref "U1") (pin "50") (pinfunction "PTA0/UART0_CTS_b/UART0_COL_b/FTM0_CH5/XB_IN4/EWM_IN/JTAG_TCLK/SWD_CLK_50") (pintype "bidirectional"))
    )
    (net (code "74") (name "/SWDIO") (class "Default")
      (node (ref "P1") (pin "2") (pinfunction "2_2") (pintype "passive"))
      (node (ref "U1") (pin "53") (pinfunction "PTA3/UART0_RTS_b/FTM0_CH0/XB_IN9/EWM_OUT_b/FLEXPWM0_A0/JTAG_TMS/SWD_DIO_53") (pintype "bidirectional"))
    )
    (net (code "75") (name "/SWO") (class "Default")
      (node (ref "P1") (pin "6") (pinfunction "6_6") (pintype "passive"))
      (node (ref "U1") (pin "52") (pinfunction "PTA2/UART0_TX/FTM0_CH7/CMP1_OUT/FTM2_QD_PHB/FTM1_CH0/JTAG_TDO/TRACE_SWO_52") (pintype "bidirectional"))
    )
    (net (code "76") (name "/UART0A_RX") (class "Default")
      (node (ref "U1") (pin "67") (pinfunction "PTA15/CMP3_IN1/PTA15/SPI0_SCK/UART0_RX/CAN2_RX/RMII0_TXEN/MII0_TXEN_67") (pintype "bidirectional"))
    )
    (net (code "77") (name "/UART0A_TX") (class "Default")
      (node (ref "U1") (pin "66") (pinfunction "PTA14/CMP3_IN0/SPI0_PCS0/UART0_TX/CAN2_TX/RMII0_CRS_DV/MII0_RXDV/I2C1_SCL_66") (pintype "bidirectional"))
    )
    (net (code "78") (name "/UART1_RX") (class "Default")
      (node (ref "P15") (pin "1") (pinfunction "1_1") (pintype "passive"))
      (node (ref "U1") (pin "106") (pinfunction "CMP1_IN1/LLWU_P7/SPI0_PCS1/UART1_RX/FTM0_CH2/CLKOUT/FTM3_FLT0/PTC3_106") (pintype "bidirectional"))
    )
    (net (code "79") (name "/UART1_TX") (class "Default")
      (node (ref "P15") (pin "2") (pinfunction "2_2") (pintype "passive"))
      (node (ref "U1") (pin "109") (pinfunction "LLWU_P8/SPI0_PCS0/UART1_TX/FTM0_CH3/CMP1_OUT/FB_AD11/PTC4_109") (pintype "bidirectional"))
    )
    (net (code "80") (name "/UART2_RX") (class "Default")
      (node (ref "P16") (pin "2") (pinfunction "2_2") (pintype "passive"))
      (node (ref "U1") (pin "19") (pinfunction "HSADC0A_CH1/ADC0_SE9/ADC0_DM1/LLWU_P19/SPI0_SCK/UART2_RX/FTM_CLKIN1/LPTMR0_ALT3/PTE17_19") (pintype "bidirectional"))
    )
    (net (code "81") (name "/UART2_TX") (class "Default")
      (node (ref "P16") (pin "1") (pinfunction "1_1") (pintype "passive"))
      (node (ref "U1") (pin "18") (pinfunction "HSADC0A_CH0/ADC0_SE1/ADC0_DP1/SPI0_PCS0/UART2_TX/FTM_CLKIN0/FTM0_FLT3/PTE16_18") (pintype "bidirectional"))
    )
    (net (code "82") (name "/UART3_RXD") (class "Default")
      (node (ref "P1") (pin "5") (pinfunction "5_5") (pintype "passive"))
      (node (ref "U1") (pin "91") (pinfunction "PTB10/HSADC0B_CH6/SPI1_PCS0/UART3_RX/ENET0_1588_TMR3/FTM0_FLT1/FB_AD19_91") (pintype "bidirectional"))
    )
    (net (code "83") (name "/UART3_TXD") (class "Default")
      (node (ref "P1") (pin "3") (pinfunction "3_3") (pintype "passive"))
      (node (ref "U1") (pin "92") (pinfunction "PTB11/HSADC0B_CH7/SPI1_SCK/UART3_TX/FTM0_FLT2/FB_AD18_92") (pintype "bidirectional"))
    )
    (net (code "84") (name "/UART4_RX") (class "Default")
      (node (ref "U1") (pin "46") (pinfunction "HSADC0B_CH5/HSADC1B_CH5/LLWU_P21/CAN1_RX/FTM0_CH1/XB_IN3/I2C0_SDA/EWM_IN/XB_OUT5/UART4_RX/PTE25_46") (pintype "bidirectional"))
    )
    (net (code "85") (name "/UART4_TX") (class "Default")
      (node (ref "U1") (pin "45") (pinfunction "HSADC0B_CH4/HSADC1B_CH4/CAN1_TX/FTM0_CH0/XB_IN2/I2C0_SCL/EWM_OUT_b/XB_OUT4/UART4_TX/PTE24_45") (pintype "bidirectional"))
    )
    (net (code "86") (name "/XTAL_0") (class "Default")
      (node (ref "C25") (pin "1") (pinfunction "1_1") (pintype "passive"))
      (node (ref "R9") (pin "2") (pinfunction "2_2") (pintype "passive"))
      (node (ref "U1") (pin "73") (pinfunction "PTA19/XTAL0/XB_IN8/FTM1_FLT0/FTM_CLKIN1/XB_OUT9/LPTMR0_ALT1_73") (pintype "bidirectional"))
      (node (ref "X1") (pin "1") (pinfunction "1_1") (pintype "passive"))
    )
    (net (code "87") (name "/XTAL_1") (class "Default")
      (node (ref "C24") (pin "1") (pinfunction "1_1") (pintype "passive"))
      (node (ref "R9") (pin "1") (pinfunction "1_1") (pintype "passive"))
      (node (ref "U1") (pin "72") (pinfunction "PTA18/EXTAL0/XB_IN7/FTM0_FLT2/FTM_CLKIN0/XB_OUT8/FTM3_CH2_72") (pintype "bidirectional"))
      (node (ref "X1") (pin "3") (pinfunction "3_3") (pintype "passive"))
    )
    (net (code "88") (name "/~{RESET}") (class "Default")
      (node (ref "C11") (pin "1") (pinfunction "1_1") (pintype "passive"))
      (node (ref "P1") (pin "10") (pinfunction "10_10") (pintype "passive"))
      (node (ref "R11") (pin "2") (pinfunction "2_2") (pintype "output"))
      (node (ref "S1") (pin "2") (pinfunction "2_2") (pintype "passive"))
      (node (ref "U1") (pin "74") (pinfunction "RESET_B_74") (pintype "input"))
    )
    (net (code "89") (name "GND") (class "Default")
      (node (ref "C1") (pin "2") (pinfunction "2_2") (pintype "passive"))
      (node (ref "C10") (pin "2") (pinfunction "2_2") (pintype "passive"))
      (node (ref "C11") (pin "2") (pinfunction "2_2") (pintype "passive"))
      (node (ref "C116") (pin "2") (pinfunction "2_2") (pintype "passive"))
      (node (ref "C117") (pin "2") (pinfunction "2_2") (pintype "passive"))
      (node (ref "C12") (pin "2") (pinfunction "2_2") (pintype "passive"))
      (node (ref "C13") (pin "2") (pinfunction "2_2") (pintype "passive"))
      (node (ref "C14") (pin "2") (pinfunction "2_2") (pintype "passive"))
      (node (ref "C15") (pin "2") (pinfunction "2_2") (pintype "passive"))
      (node (ref "C16") (pin "2") (pinfunction "2_2") (pintype "passive"))
      (node (ref "C17") (pin "2") (pinfunction "2_2") (pintype "passive"))
      (node (ref "C18") (pin "2") (pinfunction "2_2") (pintype "passive"))
      (node (ref "C19") (pin "2") (pinfunction "2_2") (pintype "passive"))
      (node (ref "C2") (pin "2") (pinfunction "2_2") (pintype "passive"))
      (node (ref "C20") (pin "2") (pinfunction "2_2") (pintype "passive"))
      (node (ref "C21") (pin "2") (pinfunction "2_2") (pintype "passive"))
      (node (ref "C22") (pin "2") (pinfunction "2_2") (pintype "passive"))
      (node (ref "C23") (pin "2") (pinfunction "2_2") (pintype "passive"))
      (node (ref "C24") (pin "2") (pinfunction "2_2") (pintype "passive"))
      (node (ref "C25") (pin "2") (pinfunction "2_2") (pintype "passive"))
      (node (ref "C3") (pin "2") (pinfunction "2_2") (pintype "passive"))
      (node (ref "C4") (pin "2") (pinfunction "2_2") (pintype "passive"))
      (node (ref "C7") (pin "2") (pinfunction "2_2") (pintype "passive"))
      (node (ref "C8") (pin "2") (pinfunction "2_2") (pintype "passive"))
      (node (ref "C9") (pin "2") (pinfunction "2_2") (pintype "passive"))
      (node (ref "L2") (pin "2") (pinfunction "2_2") (pintype "passive"))
      (node (ref "P1") (pin "9") (pinfunction "9_9") (pintype "passive"))
      (node (ref "P15") (pin "3") (pinfunction "3_3") (pintype "passive"))
      (node (ref "P16") (pin "3") (pinfunction "3_3") (pintype "passive"))
      (node (ref "S1") (pin "1") (pinfunction "1_1") (pintype "passive"))
      (node (ref "U1") (pin "107") (pinfunction "VSS_107") (pintype "power_in"))
      (node (ref "U1") (pin "121") (pinfunction "VSS_121") (pintype "power_in"))
      (node (ref "U1") (pin "134") (pinfunction "VSS_134") (pintype "power_in"))
      (node (ref "U1") (pin "17") (pinfunction "VSS_17") (pintype "power_in"))
      (node (ref "U1") (pin "22") (pinfunction "VSS_22") (pintype "power_in"))
      (node (ref "U1") (pin "34") (pinfunction "VSSA_34") (pintype "power_in"))
      (node (ref "U1") (pin "44") (pinfunction "VSS_44") (pintype "power_in"))
      (node (ref "U1") (pin "57") (pinfunction "VSS_57") (pintype "power_in"))
      (node (ref "U1") (pin "6") (pinfunction "VSS_6") (pintype "power_in"))
      (node (ref "U1") (pin "71") (pinfunction "VSS_71") (pintype "power_in"))
      (node (ref "U1") (pin "93") (pinfunction "VSS_93") (pintype "power_in"))
      (node (ref "X1") (pin "2") (pinfunction "GND_2") (pintype "power_in"))
      (node (ref "X1") (pin "4") (pinfunction "GND_4") (pintype "power_in"))
    )
    (net (code "90") (name "Net-(U1B-VREFH)") (class "Default")
      (node (ref "C5") (pin "1") (pinfunction "1_1") (pintype "passive"))
      (node (ref "C6") (pin "1") (pinfunction "1_1") (pintype "passive"))
      (node (ref "L1") (pin "1") (pinfunction "1_1") (pintype "passive"))
      (node (ref "U1") (pin "32") (pinfunction "VREFH_32") (pintype "power_in"))
    )
    (net (code "91") (name "Net-(U1B-VREFL)") (class "Default")
      (node (ref "C5") (pin "2") (pinfunction "2_2") (pintype "passive"))
      (node (ref "C6") (pin "2") (pinfunction "2_2") (pintype "passive"))
      (node (ref "L2") (pin "1") (pinfunction "1_1") (pintype "passive"))
      (node (ref "U1") (pin "33") (pinfunction "VREFL_33") (pintype "power_in"))
    )
    (net (code "92") (name "Net-(U1C-VDDA)") (class "Default")
      (node (ref "C12") (pin "1") (pinfunction "1_1") (pintype "passive"))
      (node (ref "C13") (pin "1") (pinfunction "1_1") (pintype "passive"))
      (node (ref "L3") (pin "2") (pinfunction "2_2") (pintype "output"))
      (node (ref "U1") (pin "31") (pinfunction "VDDA_31") (pintype "input"))
    )
    (net (code "93") (name "unconnected-(P1-Pad7)") (class "Default")
      (node (ref "P1") (pin "7") (pinfunction "7_7") (pintype "passive+no_connect"))
    )
    (net (code "94") (name "unconnected-(P1-Pad8)") (class "Default")
      (node (ref "P1") (pin "8") (pinfunction "8_8") (pintype "passive+no_connect"))
    )
    (net (code "95") (name "unconnected-(U1A-CMP2_IN4{slash}CMP0_IN0{slash}LLWU_P10{slash}SPI0_SOUT{slash}PDB0_EXTRG{slash}XB_IN3{slash}UART0_RX{slash}XB_OUT6{slash}I2C0_SCL{slash}FB_AD9{slash}PTC6-Pad111)") (class "Default")
      (node (ref "U1") (pin "111") (pinfunction "CMP2_IN4/CMP0_IN0/LLWU_P10/SPI0_SOUT/PDB0_EXTRG/XB_IN3/UART0_RX/XB_OUT6/I2C0_SCL/FB_AD9/PTC6_111") (pintype "bidirectional"))
    )
    (net (code "96") (name "unconnected-(U1A-CMP3_IN4{slash}CMP0_IN1{slash}SPI0_SIN{slash}XB_IN4{slash}UART0_TX{slash}XB_OUT7{slash}I2C0_SDA{slash}FB_AD8{slash}PTC7-Pad112)") (class "Default")
      (node (ref "U1") (pin "112") (pinfunction "CMP3_IN4/CMP0_IN1/SPI0_SIN/XB_IN4/UART0_TX/XB_OUT7/I2C0_SDA/FB_AD8/PTC7_112") (pintype "bidirectional"))
    )
    (net (code "97") (name "unconnected-(U1A-DAC0_OUT{slash}CMP1_IN3{slash}HSADC0A_CH5{slash}FTM0_CH3{slash}FTM_CLKIN1{slash}PTE30-Pad38)") (class "Default")
      (node (ref "U1") (pin "38") (pinfunction "DAC0_OUT/CMP1_IN3/HSADC0A_CH5/FTM0_CH3/FTM_CLKIN1/PTE30_38") (pintype "bidirectional"))
    )
    (net (code "98") (name "unconnected-(U1A-FTM2_CH0{slash}XB_IN2{slash}FTM2_QD_PHA{slash}PTE22-Pad41)") (class "Default")
      (node (ref "U1") (pin "41") (pinfunction "FTM2_CH0/XB_IN2/FTM2_QD_PHA/PTE22_41") (pintype "bidirectional"))
    )
    (net (code "99") (name "unconnected-(U1A-HSADC0A_CH2{slash}HSADC1A_CH2-Pad27)") (class "Default")
      (node (ref "U1") (pin "27") (pinfunction "HSADC0A_CH2/HSADC1A_CH2_27") (pintype "input+no_connect"))
    )
    (net (code "100") (name "unconnected-(U1A-HSADC0A_CH3{slash}HSADC1A_CH3-Pad28)") (class "Default")
      (node (ref "U1") (pin "28") (pinfunction "HSADC0A_CH3/HSADC1A_CH3_28") (pintype "input+no_connect"))
    )
    (net (code "101") (name "unconnected-(U1A-HSADC0A_CH4{slash}CMP1_IN5{slash}CMP0_IN5{slash}FTM0_CH2{slash}FTM_CLKIN0{slash}PTE29-Pad37)") (class "Default")
      (node (ref "U1") (pin "37") (pinfunction "HSADC0A_CH4/CMP1_IN5/CMP0_IN5/FTM0_CH2/FTM_CLKIN0/PTE29_37") (pintype "bidirectional"))
    )
    (net (code "102") (name "unconnected-(U1A-HSADC0A_CH6{slash}ADC0_SE7a-Pad23)") (class "Default")
      (node (ref "U1") (pin "23") (pinfunction "HSADC0A_CH6/ADC0_SE7a_23") (pintype "input+no_connect"))
    )
    (net (code "103") (name "unconnected-(U1A-HSADC0A_CH7{slash}ADC0_SE4b-Pad24)") (class "Default")
      (node (ref "U1") (pin "24") (pinfunction "HSADC0A_CH7/ADC0_SE4b_24") (pintype "input+no_connect"))
    )
    (net (code "104") (name "unconnected-(U1A-HSADC0A_CH10{slash}HSADC1B_CH2-Pad29)") (class "Default")
      (node (ref "U1") (pin "29") (pinfunction "HSADC0A_CH10/HSADC1B_CH2_29") (pintype "input+no_connect"))
    )
    (net (code "105") (name "unconnected-(U1A-HSADC0A_CH11{slash}HSADC1B_CH3-Pad30)") (class "Default")
      (node (ref "U1") (pin "30") (pinfunction "HSADC0A_CH11/HSADC1B_CH3_30") (pintype "input+no_connect"))
    )
    (net (code "106") (name "unconnected-(U1A-HSADC0A_CH12{slash}CMP0_IN4{slash}CMP2_IN3-Pad39)") (class "Default")
      (node (ref "U1") (pin "39") (pinfunction "HSADC0A_CH12/CMP0_IN4/CMP2_IN3_39") (pintype "bidirectional"))
    )
    (net (code "107") (name "unconnected-(U1A-HSADC0B_CH0{slash}ADC0_SE5a{slash}LLWU_P20{slash}SPI0_SOUT{slash}UART2_CTS_b{slash}I2C0_SDA{slash}PTE18-Pad20)") (class "Default")
      (node (ref "U1") (pin "20") (pinfunction "HSADC0B_CH0/ADC0_SE5a/LLWU_P20/SPI0_SOUT/UART2_CTS_b/I2C0_SDA/PTE18_20") (pintype "bidirectional"))
    )
    (net (code "108") (name "unconnected-(U1A-HSADC0B_CH1{slash}ADC0_SE6a{slash}SPI0_SIN{slash}UART2_RTS_b{slash}I2C0_SCL{slash}CMP3_OUT{slash}PTE19-Pad21)") (class "Default")
      (node (ref "U1") (pin "21") (pinfunction "HSADC0B_CH1/ADC0_SE6a/SPI0_SIN/UART2_RTS_b/I2C0_SCL/CMP3_OUT/PTE19_21") (pintype "bidirectional"))
    )
    (net (code "109") (name "unconnected-(U1A-HSADC1A_CH6{slash}ADC0_SE3{slash}ADC0_DP3{slash}UART5_RTS_b{slash}FLEXPW1_A3{slash}FTM3_CH6{slash}PTE11-Pad14)") (class "Default")
      (node (ref "U1") (pin "14") (pinfunction "HSADC1A_CH6/ADC0_SE3/ADC0_DP3/UART5_RTS_b/FLEXPW1_A3/FTM3_CH6/PTE11_14") (pintype "bidirectional"))
    )
    (net (code "110") (name "unconnected-(U1A-HSADC1A_CH11{slash}SPI0_SCK{slash}UART2_CTS_b{slash}FTM3_CH1{slash}FTM0_CH1{slash}FLEXPWM{slash}0_B0{slash}FB_CS0_b{slash}FLEXPWM{slash}1_B0{slash}PTD1-Pad128)") (class "Default")
      (node (ref "U1") (pin "128") (pinfunction "HSADC1A_CH11/SPI0_SCK/UART2_CTS_b/FTM3_CH1/FTM0_CH1/FLEXPWM/0_B0/FB_CS0_b/FLEXPWM/1_B0/PTD1_128") (pintype "bidirectional"))
    )
    (net (code "111") (name "unconnected-(U1A-HSADC1B_CH6{slash}ADC0_SE11{slash}ADC0_DM3{slash}FLEXPWM1_B3{slash}FTM3_CH7{slash}PTE12-Pad15)") (class "Default")
      (node (ref "U1") (pin "15") (pinfunction "HSADC1B_CH6/ADC0_SE11/ADC0_DM3/FLEXPWM1_B3/FTM3_CH7/PTE12_15") (pintype "bidirectional"))
    )
    (net (code "112") (name "unconnected-(U1A-LLWU_P12{slash}SPI0_PCS0{slash}UART2_RTS_b{slash}FTM3_CH0{slash}FTM0_CH0{slash}FLEXPWM{slash}0_A0{slash}FB_ALE{slash}FB_CS1_b{slash}FB_TS_b{slash}FLEXPWM{slash}1_A0{slash}PTD0-Pad127)") (class "Default")
      (node (ref "U1") (pin "127") (pinfunction "LLWU_P12/SPI0_PCS0/UART2_RTS_b/FTM3_CH0/FTM0_CH0/FLEXPWM/0_A0/FB_ALE/FB_CS1_b/FB_TS_b/FLEXPWM/1_A0/PTD0_127") (pintype "bidirectional"))
    )
    (net (code "113") (name "unconnected-(U1A-LLWU_P13{slash}SPI0_SOUT{slash}UART2_RX{slash}FTM3_CH2{slash}FTM0_CH2{slash}FLEXPWM{slash}0_A1{slash}I2C0_SCL{slash}FB_AD4{slash}FLEXPWM{slash}1_A1{slash}PTD2-Pad129)") (class "Default")
      (node (ref "U1") (pin "129") (pinfunction "LLWU_P13/SPI0_SOUT/UART2_RX/FTM3_CH2/FTM0_CH2/FLEXPWM/0_A1/I2C0_SCL/FB_AD4/FLEXPWM/1_A1/PTD2_129") (pintype "bidirectional"))
    )
    (net (code "114") (name "unconnected-(U1A-LLWU_P17{slash}UART5_RX{slash}FLEXPWM1_A2{slash}FTM3_CH4{slash}PTE9-Pad12)") (class "Default")
      (node (ref "U1") (pin "12") (pinfunction "LLWU_P17/UART5_RX/FLEXPWM1_A2/FTM3_CH4/PTE9_12") (pintype "bidirectional"))
    )
    (net (code "115") (name "unconnected-(U1A-LLWU_P18{slash}UART5_CTS_b{slash}FLEXPWM1_B2{slash}FTM3_CH5{slash}PTE10-Pad13)") (class "Default")
      (node (ref "U1") (pin "13") (pinfunction "LLWU_P18/UART5_CTS_b/FLEXPWM1_B2/FTM3_CH5/PTE10_13") (pintype "bidirectional"))
    )
    (net (code "116") (name "unconnected-(U1A-PTA1{slash}UART0_RX{slash}FTM0_CH6{slash}CMP0_OUT{slash}FTM2_QD_PHA{slash}FTM1_CH1{slash}JTAG_TDI-Pad51)") (class "Default")
      (node (ref "U1") (pin "51") (pinfunction "PTA1/UART0_RX/FTM0_CH6/CMP0_OUT/FTM2_QD_PHA/FTM1_CH1/JTAG_TDI_51") (pintype "bidirectional"))
    )
    (net (code "117") (name "unconnected-(U1A-PTA6{slash}FTM0_CH3{slash}CLKOUT{slash}TRACE_CLKOUT-Pad58)") (class "Default")
      (node (ref "U1") (pin "58") (pinfunction "PTA6/FTM0_CH3/CLKOUT/TRACE_CLKOUT_58") (pintype "bidirectional"))
    )
    (net (code "118") (name "unconnected-(U1A-PTB2{slash}HSADC0A_CH14{slash}CMP2_IN2{slash}I2C0_SCL{slash}UART0_RTS_b{slash}FTM0_FLT1{slash}ENET0_1588_TMR0{slash}FTM0_FLT3-Pad83)") (class "Default")
      (node (ref "U1") (pin "83") (pinfunction "PTB2/HSADC0A_CH14/CMP2_IN2/I2C0_SCL/UART0_RTS_b/FTM0_FLT1/ENET0_1588_TMR0/FTM0_FLT3_83") (pintype "bidirectional"))
    )
    (net (code "119") (name "unconnected-(U1A-PTB3{slash}HSADC0B_CH15{slash}CMP3_IN5{slash}I2C0_SDA{slash}UART0_CTS_b{slash}UART0_COL_b{slash}ENET0_1588_TMR1{slash}FTM0_FLT0-Pad84)") (class "Default")
      (node (ref "U1") (pin "84") (pinfunction "PTB3/HSADC0B_CH15/CMP3_IN5/I2C0_SDA/UART0_CTS_b/UART0_COL_b/ENET0_1588_TMR1/FTM0_FLT0_84") (pintype "bidirectional"))
    )
    (net (code "120") (name "unconnected-(U1A-PTB4{slash}ADC0_SE6b{slash}FLEXPWM{slash}1_X0{slash}ENET0_1588_TMR2{slash}FTM1_FLT0-Pad85)") (class "Default")
      (node (ref "U1") (pin "85") (pinfunction "PTB4/ADC0_SE6b/FLEXPWM/1_X0/ENET0_1588_TMR2/FTM1_FLT0_85") (pintype "bidirectional"))
    )
    (net (code "121") (name "unconnected-(U1A-PTB7{slash}HSADC1A_CH13{slash}CAN2_RX{slash}FLEXPWM{slash}1_X3{slash}FB_AD22-Pad88)") (class "Default")
      (node (ref "U1") (pin "88") (pinfunction "PTB7/HSADC1A_CH13/CAN2_RX/FLEXPWM/1_X3/FB_AD22_88") (pintype "bidirectional"))
    )
    (net (code "122") (name "unconnected-(U1A-PTB8{slash}UART3_RTS_b{slash}FB_AD21-Pad89)") (class "Default")
      (node (ref "U1") (pin "89") (pinfunction "PTB8/UART3_RTS_b/FB_AD21_89") (pintype "bidirectional"))
    )
    (net (code "123") (name "unconnected-(U1A-PTB9{slash}SPI1_PCS1{slash}UART3_CTS_b{slash}ENET0_1588_TMR2{slash}FB_AD20-Pad90)") (class "Default")
      (node (ref "U1") (pin "90") (pinfunction "PTB9/SPI1_PCS1/UART3_CTS_b/ENET0_1588_TMR2/FB_AD20_90") (pintype "bidirectional"))
    )
    (net (code "124") (name "unconnected-(U1A-PTB16{slash}SPI1_SOUT{slash}UART0_RX{slash}FTM_CLKIN2{slash}CAN0_TX{slash}EWM_IN{slash}XB_IN5{slash}FB_AD17-Pad95)") (class "Default")
      (node (ref "U1") (pin "95") (pinfunction "PTB16/SPI1_SOUT/UART0_RX/FTM_CLKIN2/CAN0_TX/EWM_IN/XB_IN5/FB_AD17_95") (pintype "bidirectional"))
    )
    (net (code "125") (name "unconnected-(U1A-PTB17{slash}SPI1_SIN{slash}UART0_TX{slash}FTM_CLKIN1{slash}CAN0_RX{slash}EWM_OUT_b{slash}FB_AD16-Pad96)") (class "Default")
      (node (ref "U1") (pin "96") (pinfunction "PTB17/SPI1_SIN/UART0_TX/FTM_CLKIN1/CAN0_RX/EWM_OUT_b/FB_AD16_96") (pintype "bidirectional"))
    )
    (net (code "126") (name "unconnected-(U1A-PTE13-Pad40)") (class "Default")
      (node (ref "U1") (pin "40") (pinfunction "PTE13_40") (pintype "bidirectional"))
    )
    (net (code "127") (name "unconnected-(U1A-PTE20{slash}HSADC0A{slash}ADC0_SE5b{slash}FTM1_CH0{slash}UART0_TX{slash}FTM1_QD_PHA-Pad25)") (class "Default")
      (node (ref "U1") (pin "25") (pinfunction "PTE20/HSADC0A/ADC0_SE5b/FTM1_CH0/UART0_TX/FTM1_QD_PHA_25") (pintype "input+no_connect"))
    )
    (net (code "128") (name "unconnected-(U1A-PTE21{slash}HSADC0A_CH9{slash}HSADC1A_CH7{slash}XB_IN9{slash}FTM1_CH1{slash}UART0_RX{slash}FTM1_QD_PHB-Pad26)") (class "Default")
      (node (ref "U1") (pin "26") (pinfunction "PTE21/HSADC0A_CH9/HSADC1A_CH7/XB_IN9/FTM1_CH1/UART0_RX/FTM1_QD_PHB_26") (pintype "input+no_connect"))
    )
    (net (code "129") (name "unconnected-(U1A-SPI0_SIN{slash}UART2_TX{slash}FTM3_CH3{slash}FTM0_CH3{slash}FLEXPWM{slash}0_B1{slash}I2C0_SDA{slash}FB_AD3{slash}FLEXPWM{slash}1_B1{slash}PTD3-Pad130)") (class "Default")
      (node (ref "U1") (pin "130") (pinfunction "SPI0_SIN/UART2_TX/FTM3_CH3/FTM0_CH3/FLEXPWM/0_B1/I2C0_SDA/FB_AD3/FLEXPWM/1_B1/PTD3_130") (pintype "bidirectional"))
    )
  )
)
